# led_show.net
KiCad netlist of a schematic drawn in Altium Designer
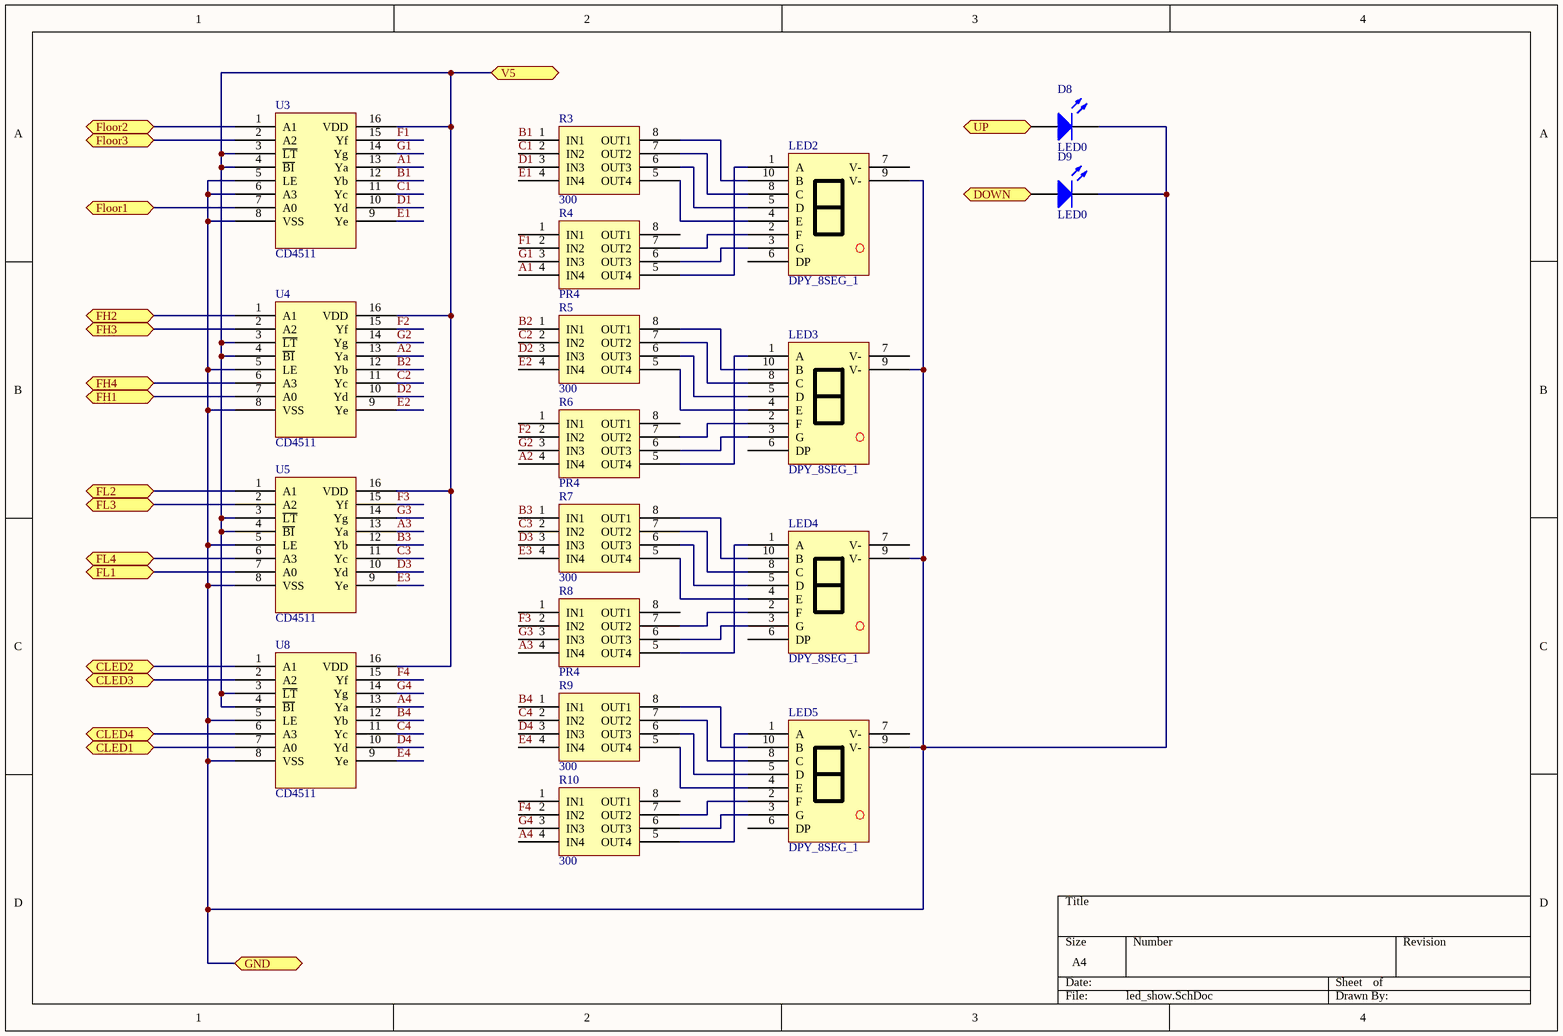
[diagram p0: led_show.SchDoc]

(export (version "E")
  (design (tool "Eeschema 10.0.6"))
  (components
    (comp (ref "D8")
      (value "LED0")
      (footprint "1206")
      (description "Typical INFRARED GaAs LED")
      (fields (field (name "PUBLISHER") "Altium Limited"))
      (libsource (lib "Miscellaneous Devices") (part "LED0"))
    )
    (comp (ref "D9")
      (value "LED0")
      (footprint "1206")
      (description "Typical INFRARED GaAs LED")
      (fields (field (name "PUBLISHER") "Altium Limited"))
      (libsource (lib "Miscellaneous Devices") (part "LED0"))
    )
    (comp (ref "LED2") (value "DPY_8SEG_1") (footprint "LED_SEG8") (libsource (lib "mylib") (part "DPY8_1")))
    (comp (ref "LED3") (value "DPY_8SEG_1") (footprint "LED_SEG8") (libsource (lib "mylib") (part "DPY8_1")))
    (comp (ref "LED4") (value "DPY_8SEG_1") (footprint "LED_SEG8") (libsource (lib "mylib") (part "DPY8_1")))
    (comp (ref "LED5") (value "DPY_8SEG_1") (footprint "LED_SEG8") (libsource (lib "mylib") (part "DPY8_1")))
    (comp (ref "R3") (value "300") (footprint "PR_4R") (libsource (lib "mylib") (part "PResister")))
    (comp (ref "R4") (value "PR4") (footprint "PR_4R") (libsource (lib "mylib") (part "PResister")))
    (comp (ref "R5") (value "300") (footprint "PR_4R") (libsource (lib "mylib") (part "PResister")))
    (comp (ref "R6") (value "PR4") (footprint "PR_4R") (libsource (lib "mylib") (part "PResister")))
    (comp (ref "R7") (value "300") (footprint "PR_4R") (libsource (lib "mylib") (part "PResister")))
    (comp (ref "R8") (value "PR4") (footprint "PR_4R") (libsource (lib "mylib") (part "PResister")))
    (comp (ref "R9") (value "300") (footprint "PR_4R") (libsource (lib "mylib") (part "PResister")))
    (comp (ref "R10") (value "300") (footprint "PR_4R") (libsource (lib "mylib") (part "PResister")))
    (comp (ref "U3") (value "CD4511") (footprint "SOP-16") (libsource (lib "mylib") (part "CD4511")))
    (comp (ref "U4") (value "CD4511") (footprint "SOP-16") (libsource (lib "mylib") (part "CD4511")))
    (comp (ref "U5") (value "CD4511") (footprint "SOP-16") (libsource (lib "mylib") (part "CD4511")))
    (comp (ref "U8") (value "CD4511") (footprint "SOP-16") (libsource (lib "mylib") (part "CD4511")))
  )
  (nets
    (net (code "1") (name "/A1") (class "Default")
      (node (ref "R4") (pin "4") (pinfunction "IN4_4") (pintype "passive"))
      (node (ref "U3") (pin "13") (pinfunction "Ya_13") (pintype "passive"))
    )
    (net (code "2") (name "/A2") (class "Default")
      (node (ref "R6") (pin "4") (pinfunction "IN4_4") (pintype "passive"))
      (node (ref "U4") (pin "13") (pinfunction "Ya_13") (pintype "passive"))
    )
    (net (code "3") (name "/A3") (class "Default")
      (node (ref "R8") (pin "4") (pinfunction "IN4_4") (pintype "passive"))
      (node (ref "U5") (pin "13") (pinfunction "Ya_13") (pintype "passive"))
    )
    (net (code "4") (name "/A4") (class "Default")
      (node (ref "R10") (pin "4") (pinfunction "IN4_4") (pintype "passive"))
      (node (ref "U8") (pin "13") (pinfunction "Ya_13") (pintype "passive"))
    )
    (net (code "5") (name "/B1") (class "Default")
      (node (ref "R3") (pin "1") (pinfunction "IN1_1") (pintype "passive"))
      (node (ref "U3") (pin "12") (pinfunction "Yb_12") (pintype "passive"))
    )
    (net (code "6") (name "/B2") (class "Default")
      (node (ref "R5") (pin "1") (pinfunction "IN1_1") (pintype "passive"))
      (node (ref "U4") (pin "12") (pinfunction "Yb_12") (pintype "passive"))
    )
    (net (code "7") (name "/B3") (class "Default")
      (node (ref "R7") (pin "1") (pinfunction "IN1_1") (pintype "passive"))
      (node (ref "U5") (pin "12") (pinfunction "Yb_12") (pintype "passive"))
    )
    (net (code "8") (name "/B4") (class "Default")
      (node (ref "R9") (pin "1") (pinfunction "IN1_1") (pintype "passive"))
      (node (ref "U8") (pin "12") (pinfunction "Yb_12") (pintype "passive"))
    )
    (net (code "9") (name "/C1") (class "Default")
      (node (ref "R3") (pin "2") (pinfunction "IN2_2") (pintype "passive"))
      (node (ref "U3") (pin "11") (pinfunction "Yc_11") (pintype "passive"))
    )
    (net (code "10") (name "/C2") (class "Default")
      (node (ref "R5") (pin "2") (pinfunction "IN2_2") (pintype "passive"))
      (node (ref "U4") (pin "11") (pinfunction "Yc_11") (pintype "passive"))
    )
    (net (code "11") (name "/C3") (class "Default")
      (node (ref "R7") (pin "2") (pinfunction "IN2_2") (pintype "passive"))
      (node (ref "U5") (pin "11") (pinfunction "Yc_11") (pintype "passive"))
    )
    (net (code "12") (name "/C4") (class "Default")
      (node (ref "R9") (pin "2") (pinfunction "IN2_2") (pintype "passive"))
      (node (ref "U8") (pin "11") (pinfunction "Yc_11") (pintype "passive"))
    )
    (net (code "13") (name "/CLED1") (class "Default")
      (node (ref "U8") (pin "7") (pinfunction "A0_7") (pintype "passive"))
    )
    (net (code "14") (name "/CLED2") (class "Default")
      (node (ref "U8") (pin "1") (pinfunction "A1_1") (pintype "passive"))
    )
    (net (code "15") (name "/CLED3") (class "Default")
      (node (ref "U8") (pin "2") (pinfunction "A2_2") (pintype "passive"))
    )
    (net (code "16") (name "/CLED4") (class "Default")
      (node (ref "U8") (pin "6") (pinfunction "A3_6") (pintype "passive"))
    )
    (net (code "17") (name "/D1") (class "Default")
      (node (ref "R3") (pin "3") (pinfunction "IN3_3") (pintype "passive"))
      (node (ref "U3") (pin "10") (pinfunction "Yd_10") (pintype "passive"))
    )
    (net (code "18") (name "/D2") (class "Default")
      (node (ref "R5") (pin "3") (pinfunction "IN3_3") (pintype "passive"))
      (node (ref "U4") (pin "10") (pinfunction "Yd_10") (pintype "passive"))
    )
    (net (code "19") (name "/D3") (class "Default")
      (node (ref "R7") (pin "3") (pinfunction "IN3_3") (pintype "passive"))
      (node (ref "U5") (pin "10") (pinfunction "Yd_10") (pintype "passive"))
    )
    (net (code "20") (name "/D4") (class "Default")
      (node (ref "R9") (pin "3") (pinfunction "IN3_3") (pintype "passive"))
      (node (ref "U8") (pin "10") (pinfunction "Yd_10") (pintype "passive"))
    )
    (net (code "21") (name "/DOWN") (class "Default")
      (node (ref "D9") (pin "1") (pinfunction "A_1") (pintype "passive"))
    )
    (net (code "22") (name "/E1") (class "Default")
      (node (ref "R3") (pin "4") (pinfunction "IN4_4") (pintype "passive"))
      (node (ref "U3") (pin "9") (pinfunction "Ye_9") (pintype "passive"))
    )
    (net (code "23") (name "/E2") (class "Default")
      (node (ref "R5") (pin "4") (pinfunction "IN4_4") (pintype "passive"))
      (node (ref "U4") (pin "9") (pinfunction "Ye_9") (pintype "passive"))
    )
    (net (code "24") (name "/E3") (class "Default")
      (node (ref "R7") (pin "4") (pinfunction "IN4_4") (pintype "passive"))
      (node (ref "U5") (pin "9") (pinfunction "Ye_9") (pintype "passive"))
    )
    (net (code "25") (name "/E4") (class "Default")
      (node (ref "R9") (pin "4") (pinfunction "IN4_4") (pintype "passive"))
      (node (ref "U8") (pin "9") (pinfunction "Ye_9") (pintype "passive"))
    )
    (net (code "26") (name "/F1") (class "Default")
      (node (ref "R4") (pin "2") (pinfunction "IN2_2") (pintype "passive"))
      (node (ref "U3") (pin "15") (pinfunction "Yf_15") (pintype "passive"))
    )
    (net (code "27") (name "/F2") (class "Default")
      (node (ref "R6") (pin "2") (pinfunction "IN2_2") (pintype "passive"))
      (node (ref "U4") (pin "15") (pinfunction "Yf_15") (pintype "passive"))
    )
    (net (code "28") (name "/F3") (class "Default")
      (node (ref "R8") (pin "2") (pinfunction "IN2_2") (pintype "passive"))
      (node (ref "U5") (pin "15") (pinfunction "Yf_15") (pintype "passive"))
    )
    (net (code "29") (name "/F4") (class "Default")
      (node (ref "R10") (pin "2") (pinfunction "IN2_2") (pintype "passive"))
      (node (ref "U8") (pin "15") (pinfunction "Yf_15") (pintype "passive"))
    )
    (net (code "30") (name "/FH1") (class "Default")
      (node (ref "U4") (pin "7") (pinfunction "A0_7") (pintype "passive"))
    )
    (net (code "31") (name "/FH2") (class "Default")
      (node (ref "U4") (pin "1") (pinfunction "A1_1") (pintype "passive"))
    )
    (net (code "32") (name "/FH3") (class "Default")
      (node (ref "U4") (pin "2") (pinfunction "A2_2") (pintype "passive"))
    )
    (net (code "33") (name "/FH4") (class "Default")
      (node (ref "U4") (pin "6") (pinfunction "A3_6") (pintype "passive"))
    )
    (net (code "34") (name "/FL1") (class "Default")
      (node (ref "U5") (pin "7") (pinfunction "A0_7") (pintype "passive"))
    )
    (net (code "35") (name "/FL2") (class "Default")
      (node (ref "U5") (pin "1") (pinfunction "A1_1") (pintype "passive"))
    )
    (net (code "36") (name "/FL3") (class "Default")
      (node (ref "U5") (pin "2") (pinfunction "A2_2") (pintype "passive"))
    )
    (net (code "37") (name "/FL4") (class "Default")
      (node (ref "U5") (pin "6") (pinfunction "A3_6") (pintype "passive"))
    )
    (net (code "38") (name "/Floor1") (class "Default")
      (node (ref "U3") (pin "7") (pinfunction "A0_7") (pintype "passive"))
    )
    (net (code "39") (name "/Floor2") (class "Default")
      (node (ref "U3") (pin "1") (pinfunction "A1_1") (pintype "passive"))
    )
    (net (code "40") (name "/Floor3") (class "Default")
      (node (ref "U3") (pin "2") (pinfunction "A2_2") (pintype "passive"))
    )
    (net (code "41") (name "/G1") (class "Default")
      (node (ref "R4") (pin "3") (pinfunction "IN3_3") (pintype "passive"))
      (node (ref "U3") (pin "14") (pinfunction "Yg_14") (pintype "passive"))
    )
    (net (code "42") (name "/G2") (class "Default")
      (node (ref "R6") (pin "3") (pinfunction "IN3_3") (pintype "passive"))
      (node (ref "U4") (pin "14") (pinfunction "Yg_14") (pintype "passive"))
    )
    (net (code "43") (name "/G3") (class "Default")
      (node (ref "R8") (pin "3") (pinfunction "IN3_3") (pintype "passive"))
      (node (ref "U5") (pin "14") (pinfunction "Yg_14") (pintype "passive"))
    )
    (net (code "44") (name "/G4") (class "Default")
      (node (ref "R10") (pin "3") (pinfunction "IN3_3") (pintype "passive"))
      (node (ref "U8") (pin "14") (pinfunction "Yg_14") (pintype "passive"))
    )
    (net (code "45") (name "/GND") (class "Default")
      (node (ref "D8") (pin "2") (pinfunction "K_2") (pintype "passive"))
      (node (ref "D9") (pin "2") (pinfunction "K_2") (pintype "passive"))
      (node (ref "LED2") (pin "9") (pinfunction "V-_9") (pintype "passive"))
      (node (ref "LED3") (pin "9") (pinfunction "V-_9") (pintype "passive"))
      (node (ref "LED4") (pin "9") (pinfunction "V-_9") (pintype "passive"))
      (node (ref "LED5") (pin "9") (pinfunction "V-_9") (pintype "passive"))
      (node (ref "U3") (pin "5") (pinfunction "LE_5") (pintype "passive"))
      (node (ref "U3") (pin "6") (pinfunction "A3_6") (pintype "passive"))
      (node (ref "U3") (pin "8") (pinfunction "VSS_8") (pintype "passive"))
      (node (ref "U4") (pin "5") (pinfunction "LE_5") (pintype "passive"))
      (node (ref "U4") (pin "8") (pinfunction "VSS_8") (pintype "passive"))
      (node (ref "U5") (pin "5") (pinfunction "LE_5") (pintype "passive"))
      (node (ref "U5") (pin "8") (pinfunction "VSS_8") (pintype "passive"))
      (node (ref "U8") (pin "5") (pinfunction "LE_5") (pintype "passive"))
      (node (ref "U8") (pin "8") (pinfunction "VSS_8") (pintype "passive"))
    )
    (net (code "46") (name "/UP") (class "Default")
      (node (ref "D8") (pin "1") (pinfunction "A_1") (pintype "passive"))
    )
    (net (code "47") (name "/V5") (class "Default")
      (node (ref "U3") (pin "16") (pinfunction "VDD_16") (pintype "passive"))
      (node (ref "U3") (pin "3") (pinfunction "~{LT}_3") (pintype "passive"))
      (node (ref "U3") (pin "4") (pinfunction "~{BI}_4") (pintype "passive"))
      (node (ref "U4") (pin "16") (pinfunction "VDD_16") (pintype "passive"))
      (node (ref "U4") (pin "3") (pinfunction "~{LT}_3") (pintype "passive"))
      (node (ref "U4") (pin "4") (pinfunction "~{BI}_4") (pintype "passive"))
      (node (ref "U5") (pin "16") (pinfunction "VDD_16") (pintype "passive"))
      (node (ref "U5") (pin "3") (pinfunction "~{LT}_3") (pintype "passive"))
      (node (ref "U5") (pin "4") (pinfunction "~{BI}_4") (pintype "passive"))
      (node (ref "U8") (pin "16") (pinfunction "VDD_16") (pintype "passive"))
      (node (ref "U8") (pin "3") (pinfunction "~{LT}_3") (pintype "passive"))
      (node (ref "U8") (pin "4") (pinfunction "~{BI}_4") (pintype "passive"))
    )
    (net (code "48") (name "Net-(LED2-A)") (class "Default")
      (node (ref "LED2") (pin "1") (pinfunction "A_1") (pintype "passive"))
      (node (ref "R4") (pin "5") (pinfunction "OUT4_5") (pintype "passive"))
    )
    (net (code "49") (name "Net-(LED2-B)") (class "Default")
      (node (ref "LED2") (pin "10") (pinfunction "B_10") (pintype "passive"))
      (node (ref "R3") (pin "8") (pinfunction "OUT1_8") (pintype "passive"))
    )
    (net (code "50") (name "Net-(LED2-C)") (class "Default")
      (node (ref "LED2") (pin "8") (pinfunction "C_8") (pintype "passive"))
      (node (ref "R3") (pin "7") (pinfunction "OUT2_7") (pintype "passive"))
    )
    (net (code "51") (name "Net-(LED2-D)") (class "Default")
      (node (ref "LED2") (pin "5") (pinfunction "D_5") (pintype "passive"))
      (node (ref "R3") (pin "6") (pinfunction "OUT3_6") (pintype "passive"))
    )
    (net (code "52") (name "Net-(LED2-E)") (class "Default")
      (node (ref "LED2") (pin "4") (pinfunction "E_4") (pintype "passive"))
      (node (ref "R3") (pin "5") (pinfunction "OUT4_5") (pintype "passive"))
    )
    (net (code "53") (name "Net-(LED2-F)") (class "Default")
      (node (ref "LED2") (pin "2") (pinfunction "F_2") (pintype "passive"))
      (node (ref "R4") (pin "7") (pinfunction "OUT2_7") (pintype "passive"))
    )
    (net (code "54") (name "Net-(LED2-G)") (class "Default")
      (node (ref "LED2") (pin "3") (pinfunction "G_3") (pintype "passive"))
      (node (ref "R4") (pin "6") (pinfunction "OUT3_6") (pintype "passive"))
    )
    (net (code "55") (name "Net-(LED3-A)") (class "Default")
      (node (ref "LED3") (pin "1") (pinfunction "A_1") (pintype "passive"))
      (node (ref "R6") (pin "5") (pinfunction "OUT4_5") (pintype "passive"))
    )
    (net (code "56") (name "Net-(LED3-B)") (class "Default")
      (node (ref "LED3") (pin "10") (pinfunction "B_10") (pintype "passive"))
      (node (ref "R5") (pin "8") (pinfunction "OUT1_8") (pintype "passive"))
    )
    (net (code "57") (name "Net-(LED3-C)") (class "Default")
      (node (ref "LED3") (pin "8") (pinfunction "C_8") (pintype "passive"))
      (node (ref "R5") (pin "7") (pinfunction "OUT2_7") (pintype "passive"))
    )
    (net (code "58") (name "Net-(LED3-D)") (class "Default")
      (node (ref "LED3") (pin "5") (pinfunction "D_5") (pintype "passive"))
      (node (ref "R5") (pin "6") (pinfunction "OUT3_6") (pintype "passive"))
    )
    (net (code "59") (name "Net-(LED3-E)") (class "Default")
      (node (ref "LED3") (pin "4") (pinfunction "E_4") (pintype "passive"))
      (node (ref "R5") (pin "5") (pinfunction "OUT4_5") (pintype "passive"))
    )
    (net (code "60") (name "Net-(LED3-F)") (class "Default")
      (node (ref "LED3") (pin "2") (pinfunction "F_2") (pintype "passive"))
      (node (ref "R6") (pin "7") (pinfunction "OUT2_7") (pintype "passive"))
    )
    (net (code "61") (name "Net-(LED3-G)") (class "Default")
      (node (ref "LED3") (pin "3") (pinfunction "G_3") (pintype "passive"))
      (node (ref "R6") (pin "6") (pinfunction "OUT3_6") (pintype "passive"))
    )
    (net (code "62") (name "Net-(LED4-A)") (class "Default")
      (node (ref "LED4") (pin "1") (pinfunction "A_1") (pintype "passive"))
      (node (ref "R8") (pin "5") (pinfunction "OUT4_5") (pintype "passive"))
    )
    (net (code "63") (name "Net-(LED4-B)") (class "Default")
      (node (ref "LED4") (pin "10") (pinfunction "B_10") (pintype "passive"))
      (node (ref "R7") (pin "8") (pinfunction "OUT1_8") (pintype "passive"))
    )
    (net (code "64") (name "Net-(LED4-C)") (class "Default")
      (node (ref "LED4") (pin "8") (pinfunction "C_8") (pintype "passive"))
      (node (ref "R7") (pin "7") (pinfunction "OUT2_7") (pintype "passive"))
    )
    (net (code "65") (name "Net-(LED4-D)") (class "Default")
      (node (ref "LED4") (pin "5") (pinfunction "D_5") (pintype "passive"))
      (node (ref "R7") (pin "6") (pinfunction "OUT3_6") (pintype "passive"))
    )
    (net (code "66") (name "Net-(LED4-E)") (class "Default")
      (node (ref "LED4") (pin "4") (pinfunction "E_4") (pintype "passive"))
      (node (ref "R7") (pin "5") (pinfunction "OUT4_5") (pintype "passive"))
    )
    (net (code "67") (name "Net-(LED4-F)") (class "Default")
      (node (ref "LED4") (pin "2") (pinfunction "F_2") (pintype "passive"))
      (node (ref "R8") (pin "7") (pinfunction "OUT2_7") (pintype "passive"))
    )
    (net (code "68") (name "Net-(LED4-G)") (class "Default")
      (node (ref "LED4") (pin "3") (pinfunction "G_3") (pintype "passive"))
      (node (ref "R8") (pin "6") (pinfunction "OUT3_6") (pintype "passive"))
    )
    (net (code "69") (name "Net-(LED5-A)") (class "Default")
      (node (ref "LED5") (pin "1") (pinfunction "A_1") (pintype "passive"))
      (node (ref "R10") (pin "5") (pinfunction "OUT4_5") (pintype "passive"))
    )
    (net (code "70") (name "Net-(LED5-B)") (class "Default")
      (node (ref "LED5") (pin "10") (pinfunction "B_10") (pintype "passive"))
      (node (ref "R9") (pin "8") (pinfunction "OUT1_8") (pintype "passive"))
    )
    (net (code "71") (name "Net-(LED5-C)") (class "Default")
      (node (ref "LED5") (pin "8") (pinfunction "C_8") (pintype "passive"))
      (node (ref "R9") (pin "7") (pinfunction "OUT2_7") (pintype "passive"))
    )
    (net (code "72") (name "Net-(LED5-D)") (class "Default")
      (node (ref "LED5") (pin "5") (pinfunction "D_5") (pintype "passive"))
      (node (ref "R9") (pin "6") (pinfunction "OUT3_6") (pintype "passive"))
    )
    (net (code "73") (name "Net-(LED5-E)") (class "Default")
      (node (ref "LED5") (pin "4") (pinfunction "E_4") (pintype "passive"))
      (node (ref "R9") (pin "5") (pinfunction "OUT4_5") (pintype "passive"))
    )
    (net (code "74") (name "Net-(LED5-F)") (class "Default")
      (node (ref "LED5") (pin "2") (pinfunction "F_2") (pintype "passive"))
      (node (ref "R10") (pin "7") (pinfunction "OUT2_7") (pintype "passive"))
    )
    (net (code "75") (name "Net-(LED5-G)") (class "Default")
      (node (ref "LED5") (pin "3") (pinfunction "G_3") (pintype "passive"))
      (node (ref "R10") (pin "6") (pinfunction "OUT3_6") (pintype "passive"))
    )
    (net (code "76") (name "unconnected-(LED2-DP-Pad6)") (class "Default")
      (node (ref "LED2") (pin "6") (pinfunction "DP_6") (pintype "passive"))
    )
    (net (code "77") (name "unconnected-(LED2-V--Pad7)") (class "Default")
      (node (ref "LED2") (pin "7") (pinfunction "V-_7") (pintype "passive"))
    )
    (net (code "78") (name "unconnected-(LED3-DP-Pad6)") (class "Default")
      (node (ref "LED3") (pin "6") (pinfunction "DP_6") (pintype "passive"))
    )
    (net (code "79") (name "unconnected-(LED3-V--Pad7)") (class "Default")
      (node (ref "LED3") (pin "7") (pinfunction "V-_7") (pintype "passive"))
    )
    (net (code "80") (name "unconnected-(LED4-DP-Pad6)") (class "Default")
      (node (ref "LED4") (pin "6") (pinfunction "DP_6") (pintype "passive"))
    )
    (net (code "81") (name "unconnected-(LED4-V--Pad7)") (class "Default")
      (node (ref "LED4") (pin "7") (pinfunction "V-_7") (pintype "passive"))
    )
    (net (code "82") (name "unconnected-(LED5-DP-Pad6)") (class "Default")
      (node (ref "LED5") (pin "6") (pinfunction "DP_6") (pintype "passive"))
    )
    (net (code "83") (name "unconnected-(LED5-V--Pad7)") (class "Default")
      (node (ref "LED5") (pin "7") (pinfunction "V-_7") (pintype "passive"))
    )
    (net (code "84") (name "unconnected-(R4-IN1-Pad1)") (class "Default")
      (node (ref "R4") (pin "1") (pinfunction "IN1_1") (pintype "passive"))
    )
    (net (code "85") (name "unconnected-(R4-OUT1-Pad8)") (class "Default")
      (node (ref "R4") (pin "8") (pinfunction "OUT1_8") (pintype "passive"))
    )
    (net (code "86") (name "unconnected-(R6-IN1-Pad1)") (class "Default")
      (node (ref "R6") (pin "1") (pinfunction "IN1_1") (pintype "passive"))
    )
    (net (code "87") (name "unconnected-(R6-OUT1-Pad8)") (class "Default")
      (node (ref "R6") (pin "8") (pinfunction "OUT1_8") (pintype "passive"))
    )
    (net (code "88") (name "unconnected-(R8-IN1-Pad1)") (class "Default")
      (node (ref "R8") (pin "1") (pinfunction "IN1_1") (pintype "passive"))
    )
    (net (code "89") (name "unconnected-(R8-OUT1-Pad8)") (class "Default")
      (node (ref "R8") (pin "8") (pinfunction "OUT1_8") (pintype "passive"))
    )
    (net (code "90") (name "unconnected-(R10-IN1-Pad1)") (class "Default")
      (node (ref "R10") (pin "1") (pinfunction "IN1_1") (pintype "passive"))
    )
    (net (code "91") (name "unconnected-(R10-OUT1-Pad8)") (class "Default")
      (node (ref "R10") (pin "8") (pinfunction "OUT1_8") (pintype "passive"))
    )
  )
)
